# fabwalker-0930-2.net
KiCad netlist of a schematic drawn in EAGLE
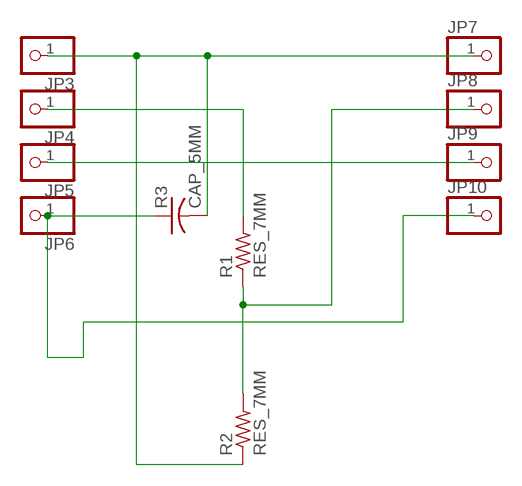
[diagram p0: schematic, sheet 1]

(export (version "E")
  (design (tool "Eeschema 10.0.6"))
  (components
    (comp (ref "JP3")
      (value "PINHD-1X1")
      (footprint "eagle-import:1X01")
      (libsource (lib "eagle-import") (part "PINHD-1X1"))
    )
    (comp (ref "JP4")
      (value "PINHD-1X1")
      (footprint "eagle-import:1X01")
      (libsource (lib "eagle-import") (part "PINHD-1X1"))
    )
    (comp (ref "JP5")
      (value "PINHD-1X1")
      (footprint "eagle-import:1X01")
      (libsource (lib "eagle-import") (part "PINHD-1X1"))
    )
    (comp (ref "JP6")
      (value "PINHD-1X1")
      (footprint "eagle-import:1X01")
      (libsource (lib "eagle-import") (part "PINHD-1X1"))
    )
    (comp (ref "JP7")
      (value "PINHD-1X1")
      (footprint "eagle-import:1X01")
      (libsource (lib "eagle-import") (part "PINHD-1X1"))
    )
    (comp (ref "JP8")
      (value "PINHD-1X1")
      (footprint "eagle-import:1X01")
      (libsource (lib "eagle-import") (part "PINHD-1X1"))
    )
    (comp (ref "JP9")
      (value "PINHD-1X1")
      (footprint "eagle-import:1X01")
      (libsource (lib "eagle-import") (part "PINHD-1X1"))
    )
    (comp (ref "JP10")
      (value "PINHD-1X1")
      (footprint "eagle-import:1X01")
      (libsource (lib "eagle-import") (part "PINHD-1X1"))
    )
    (comp (ref "R1")
      (value "RES_7MM")
      (footprint "eagle-import:0204_7")
      (libsource (lib "eagle-import") (part "RES_7MM"))
    )
    (comp (ref "R2")
      (value "RES_7MM")
      (footprint "eagle-import:0204_7")
      (libsource (lib "eagle-import") (part "RES_7MM"))
    )
    (comp (ref "R3")
      (value "CAP_5MM")
      (footprint "eagle-import:C050-030X075")
      (libsource (lib "eagle-import") (part "CAP_5MM"))
    )
  )
  (nets
    (net (code "1") (name "Net-(JP3-Pad1)") (class "Default")
      (node (ref "JP3") (pin "1") (pinfunction "1_1") (pintype "passive"))
      (node (ref "JP7") (pin "1") (pinfunction "1_1") (pintype "passive"))
      (node (ref "R2") (pin "1") (pinfunction "1_1") (pintype "passive"))
      (node (ref "R3") (pin "2") (pinfunction "2_2") (pintype "passive"))
    )
    (net (code "2") (name "Net-(JP4-Pad1)") (class "Default")
      (node (ref "JP4") (pin "1") (pinfunction "1_1") (pintype "passive"))
      (node (ref "R1") (pin "2") (pinfunction "2_2") (pintype "passive"))
    )
    (net (code "3") (name "Net-(JP5-Pad1)") (class "Default")
      (node (ref "JP5") (pin "1") (pinfunction "1_1") (pintype "passive"))
      (node (ref "JP9") (pin "1") (pinfunction "1_1") (pintype "passive"))
    )
    (net (code "4") (name "Net-(JP8-Pad1)") (class "Default")
      (node (ref "JP8") (pin "1") (pinfunction "1_1") (pintype "passive"))
      (node (ref "R1") (pin "1") (pinfunction "1_1") (pintype "passive"))
      (node (ref "R2") (pin "2") (pinfunction "2_2") (pintype "passive"))
    )
    (net (code "5") (name "Net-(JP10-Pad1)") (class "Default")
      (node (ref "JP10") (pin "1") (pinfunction "1_1") (pintype "passive"))
      (node (ref "JP6") (pin "1") (pinfunction "1_1") (pintype "passive"))
      (node (ref "R3") (pin "1") (pinfunction "1_1") (pintype "passive"))
    )
  )
)
